# radencoder_links.net
KiCad netlist of a schematic drawn in EAGLE
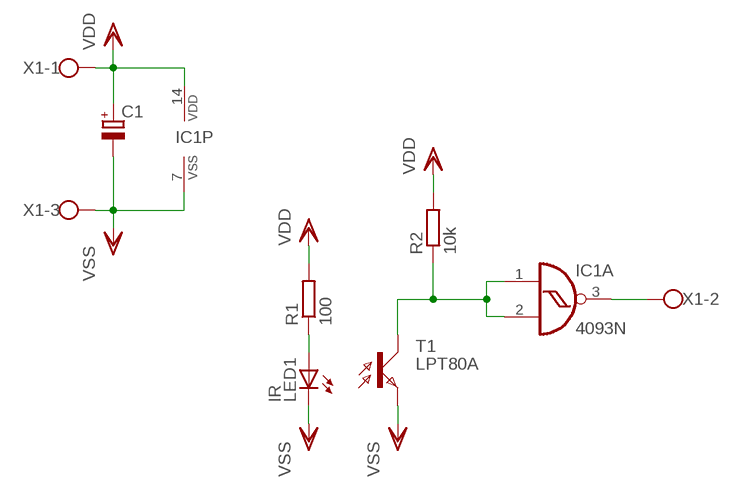
[diagram p0: schematic, sheet 1]

(export (version "E")
  (design (tool "Eeschema 10.0.6"))
  (components
    (comp (ref "C1")
      (value "CPOL-EUE5-10.5")
      (footprint "eagle-import:E5-10,5")
      (libsource (lib "eagle-import") (part "CPOL-EUE5-10.5"))
    )
    (comp (ref "IC1")
      (value "4093N")
      (footprint "eagle-import:DIL14")
      (libsource (lib "eagle-import") (part "4093N"))
    )
    (comp (ref "LED1")
      (value "IR")
      (footprint "eagle-import:LED5MM")
      (libsource (lib "eagle-import") (part "LED5MM"))
    )
    (comp (ref "R1")
      (value "100")
      (footprint "eagle-import:0207_10")
      (libsource (lib "eagle-import") (part "R-EU_0207/10"))
    )
    (comp (ref "R2")
      (value "10k")
      (footprint "eagle-import:0207_10")
      (libsource (lib "eagle-import") (part "R-EU_0207/10"))
    )
    (comp (ref "T1")
      (value "LPT80A")
      (footprint "eagle-import:LPT80A")
      (libsource (lib "eagle-import") (part "LPT80A"))
    )
    (comp (ref "X1")
      (value "W237-103")
      (footprint "eagle-import:W237-103")
      (fields (field (name "MPN") "237-103"))
      (libsource (lib "eagle-import") (part "W237-103"))
    )
  )
  (nets
    (net (code "1") (name "Net-(IC1A-I0)") (class "Default")
      (node (ref "IC1") (pin "1") (pinfunction "I0_1") (pintype "input"))
      (node (ref "IC1") (pin "2") (pinfunction "I1_2") (pintype "input"))
      (node (ref "R2") (pin "1") (pinfunction "1_1") (pintype "passive"))
      (node (ref "T1") (pin "C") (pinfunction "C_C") (pintype "passive"))
    )
    (net (code "2") (name "Net-(IC1A-O)") (class "Default")
      (node (ref "IC1") (pin "3") (pinfunction "O_3") (pintype "output"))
      (node (ref "X1") (pin "2") (pinfunction "KL_2") (pintype "passive"))
    )
    (net (code "3") (name "Net-(LED1-PadA)") (class "Default")
      (node (ref "LED1") (pin "A") (pinfunction "A_A") (pintype "passive"))
      (node (ref "R1") (pin "1") (pinfunction "1_1") (pintype "passive"))
    )
    (net (code "4") (name "VDD") (class "Default")
      (node (ref "C1") (pin "+") (pinfunction "+_+") (pintype "passive"))
      (node (ref "IC1") (pin "14") (pinfunction "VDD_14") (pintype "power_in"))
      (node (ref "R1") (pin "2") (pinfunction "2_2") (pintype "passive"))
      (node (ref "R2") (pin "2") (pinfunction "2_2") (pintype "passive"))
      (node (ref "X1") (pin "1") (pinfunction "KL_1") (pintype "passive"))
    )
    (net (code "5") (name "VSS") (class "Default")
      (node (ref "C1") (pin "-") (pinfunction "-_-") (pintype "passive"))
      (node (ref "IC1") (pin "7") (pinfunction "VSS_7") (pintype "power_in"))
      (node (ref "LED1") (pin "K") (pinfunction "C_K") (pintype "passive"))
      (node (ref "T1") (pin "E") (pinfunction "E_E") (pintype "passive"))
      (node (ref "X1") (pin "3") (pinfunction "KL_3") (pintype "passive"))
    )
  )
)
